# Qwiic_Mux.net
KiCad netlist of a schematic drawn in EAGLE
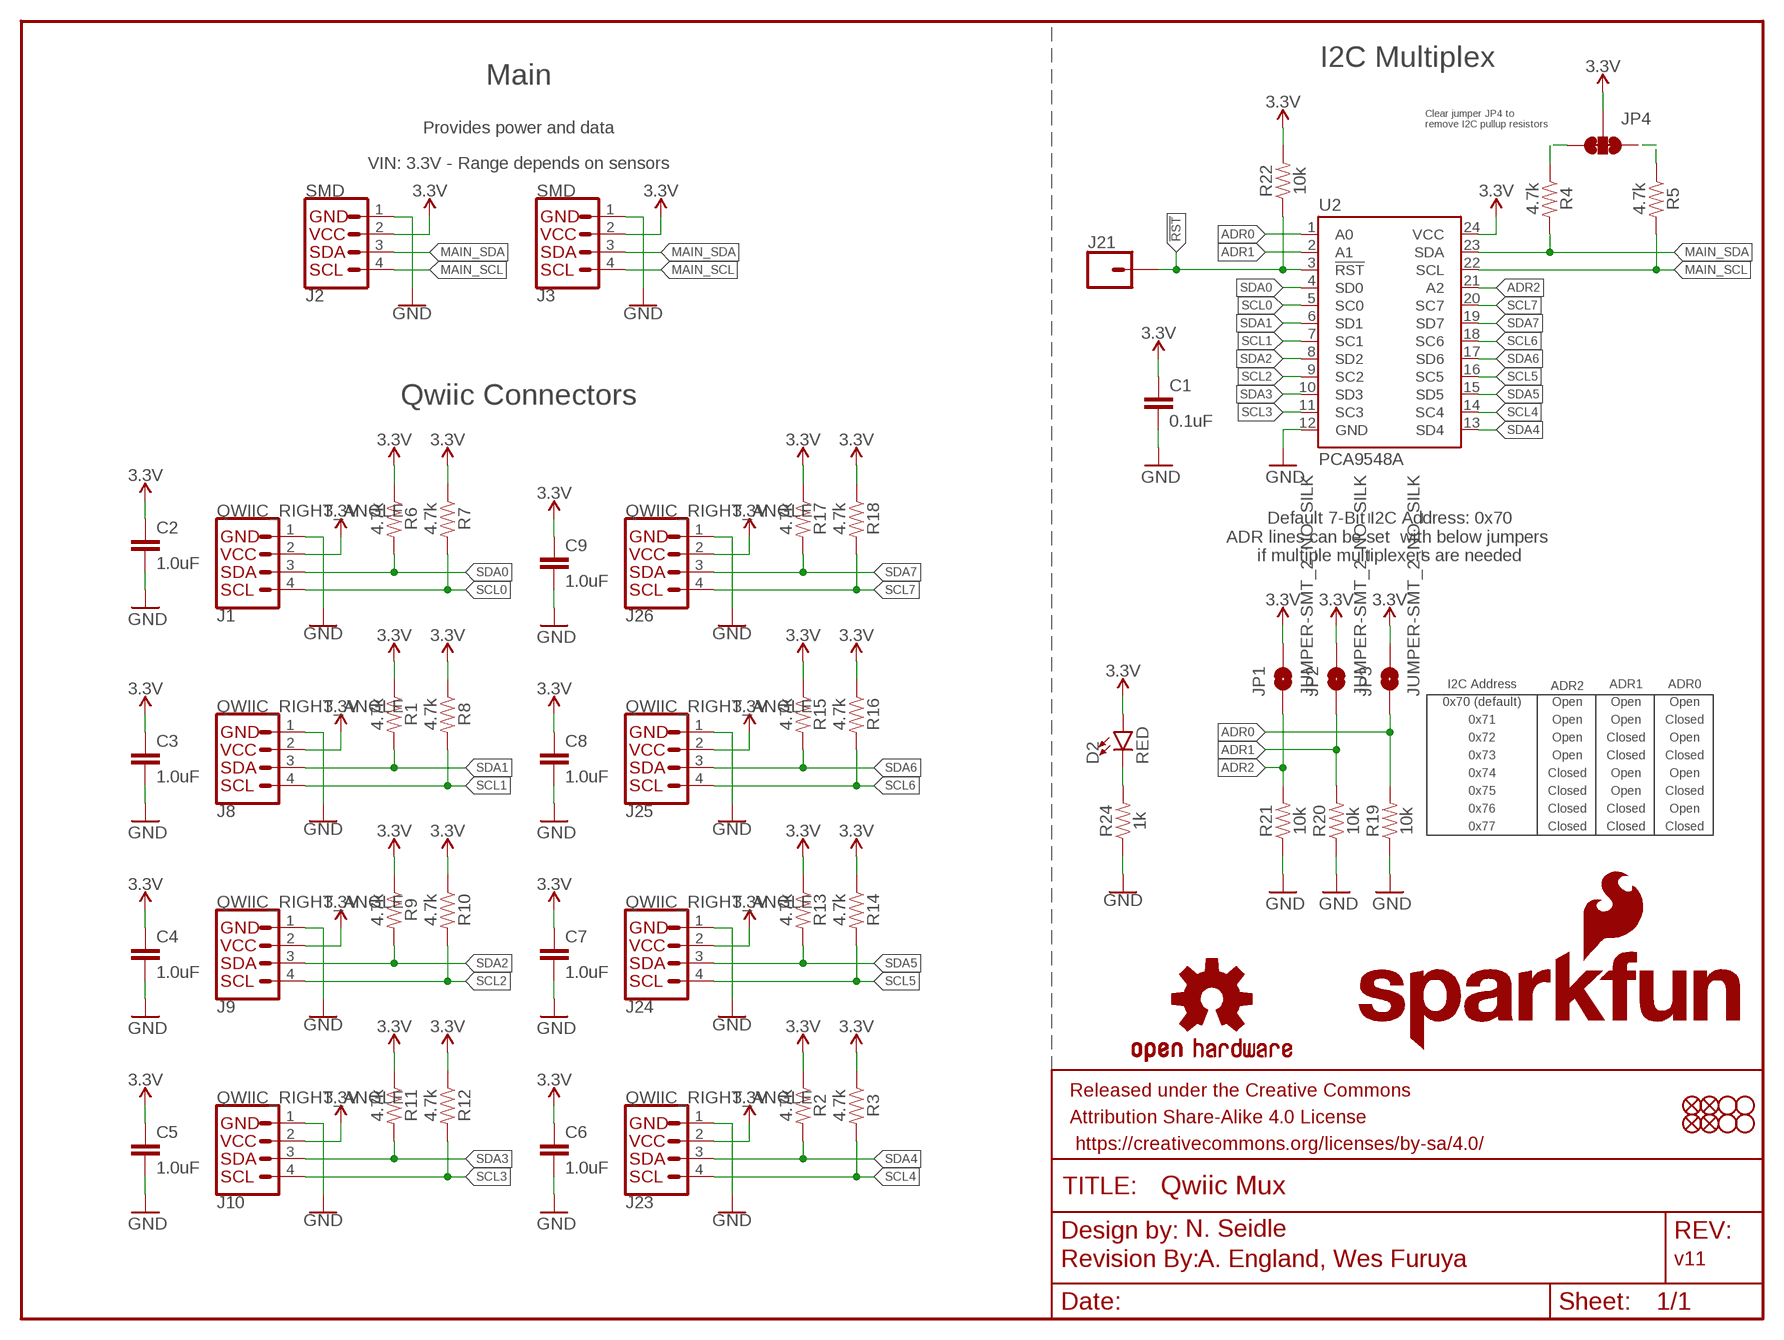
[diagram p0: schematic, sheet 1]

(export (version "E")
  (design (tool "Eeschema 10.0.6"))
  (components
    (comp (ref "C1")
      (value "0.1uF")
      (footprint "eagle-import:0603")
      (libsource (lib "eagle-import") (part "0.1UF-0603-25V-(+80/-20%)"))
    )
    (comp (ref "C2")
      (value "1.0uF")
      (footprint "eagle-import:0603")
      (libsource (lib "eagle-import") (part "1.0UF-0603-16V-10%"))
    )
    (comp (ref "C3")
      (value "1.0uF")
      (footprint "eagle-import:0603")
      (libsource (lib "eagle-import") (part "1.0UF-0603-16V-10%"))
    )
    (comp (ref "C4")
      (value "1.0uF")
      (footprint "eagle-import:0603")
      (libsource (lib "eagle-import") (part "1.0UF-0603-16V-10%"))
    )
    (comp (ref "C5")
      (value "1.0uF")
      (footprint "eagle-import:0603")
      (libsource (lib "eagle-import") (part "1.0UF-0603-16V-10%"))
    )
    (comp (ref "C6")
      (value "1.0uF")
      (footprint "eagle-import:0603")
      (libsource (lib "eagle-import") (part "1.0UF-0603-16V-10%"))
    )
    (comp (ref "C7")
      (value "1.0uF")
      (footprint "eagle-import:0603")
      (libsource (lib "eagle-import") (part "1.0UF-0603-16V-10%"))
    )
    (comp (ref "C8")
      (value "1.0uF")
      (footprint "eagle-import:0603")
      (libsource (lib "eagle-import") (part "1.0UF-0603-16V-10%"))
    )
    (comp (ref "C9")
      (value "1.0uF")
      (footprint "eagle-import:0603")
      (libsource (lib "eagle-import") (part "1.0UF-0603-16V-10%"))
    )
    (comp (ref "D2")
      (value "RED")
      (footprint "eagle-import:LED-0603")
      (libsource (lib "eagle-import") (part "LED-RED0603"))
    )
    (comp (ref "FD1")
      (value "FIDUCIAL1X2")
      (footprint "eagle-import:FIDUCIAL-1X2")
      (libsource (lib "eagle-import") (part "FIDUCIAL1X2"))
    )
    (comp (ref "FD2")
      (value "FIDUCIAL1X2")
      (footprint "eagle-import:FIDUCIAL-1X2")
      (libsource (lib "eagle-import") (part "FIDUCIAL1X2"))
    )
    (comp (ref "FD3")
      (value "FIDUCIAL1X2")
      (footprint "eagle-import:FIDUCIAL-1X2")
      (libsource (lib "eagle-import") (part "FIDUCIAL1X2"))
    )
    (comp (ref "FD4")
      (value "FIDUCIAL1X2")
      (footprint "eagle-import:FIDUCIAL-1X2")
      (libsource (lib "eagle-import") (part "FIDUCIAL1X2"))
    )
    (comp (ref "FRAME1")
      (value "FRAME-LETTER")
      (footprint "eagle-import:CREATIVE_COMMONS")
      (libsource (lib "eagle-import") (part "FRAME-LETTER"))
    )
    (comp (ref "H1")
      (value "STAND-OFF")
      (footprint "eagle-import:STAND-OFF")
      (libsource (lib "eagle-import") (part "STAND-OFF"))
    )
    (comp (ref "H2")
      (value "STAND-OFF")
      (footprint "eagle-import:STAND-OFF")
      (libsource (lib "eagle-import") (part "STAND-OFF"))
    )
    (comp (ref "H3")
      (value "STAND-OFF")
      (footprint "eagle-import:STAND-OFF")
      (libsource (lib "eagle-import") (part "STAND-OFF"))
    )
    (comp (ref "H4")
      (value "STAND-OFF")
      (footprint "eagle-import:STAND-OFF")
      (libsource (lib "eagle-import") (part "STAND-OFF"))
    )
    (comp (ref "J1")
      (value "QWIIC_RIGHT_ANGLE")
      (footprint "eagle-import:JST04_1MM_RA")
      (libsource (lib "eagle-import") (part "QWIIC_CONNECTORJS-1MM"))
    )
    (comp (ref "J2")
      (value "SMD")
      (footprint "eagle-import:1X04_1MM_RA")
      (libsource (lib "eagle-import") (part "I2C_STANDARDJS-1MM"))
    )
    (comp (ref "J3")
      (value "SMD")
      (footprint "eagle-import:1X04_1MM_RA")
      (libsource (lib "eagle-import") (part "I2C_STANDARDJS-1MM"))
    )
    (comp (ref "J8")
      (value "QWIIC_RIGHT_ANGLE")
      (footprint "eagle-import:JST04_1MM_RA")
      (libsource (lib "eagle-import") (part "QWIIC_CONNECTORJS-1MM"))
    )
    (comp (ref "J9")
      (value "QWIIC_RIGHT_ANGLE")
      (footprint "eagle-import:JST04_1MM_RA")
      (libsource (lib "eagle-import") (part "QWIIC_CONNECTORJS-1MM"))
    )
    (comp (ref "J10")
      (value "QWIIC_RIGHT_ANGLE")
      (footprint "eagle-import:JST04_1MM_RA")
      (libsource (lib "eagle-import") (part "QWIIC_CONNECTORJS-1MM"))
    )
    (comp (ref "J21")
      (value "CONN_01PTH_NO_SILK_YES_STOP")
      (footprint "eagle-import:1X01_NO_SILK")
      (libsource (lib "eagle-import") (part "CONN_01PTH_NO_SILK_YES_STOP"))
    )
    (comp (ref "J23")
      (value "QWIIC_RIGHT_ANGLE")
      (footprint "eagle-import:JST04_1MM_RA")
      (libsource (lib "eagle-import") (part "QWIIC_CONNECTORJS-1MM"))
    )
    (comp (ref "J24")
      (value "QWIIC_RIGHT_ANGLE")
      (footprint "eagle-import:JST04_1MM_RA")
      (libsource (lib "eagle-import") (part "QWIIC_CONNECTORJS-1MM"))
    )
    (comp (ref "J25")
      (value "QWIIC_RIGHT_ANGLE")
      (footprint "eagle-import:JST04_1MM_RA")
      (libsource (lib "eagle-import") (part "QWIIC_CONNECTORJS-1MM"))
    )
    (comp (ref "J26")
      (value "QWIIC_RIGHT_ANGLE")
      (footprint "eagle-import:JST04_1MM_RA")
      (libsource (lib "eagle-import") (part "QWIIC_CONNECTORJS-1MM"))
    )
    (comp (ref "JP1")
      (value "JUMPER-SMT_2_NO_SILK")
      (footprint "eagle-import:SMT-JUMPER_2_NO_SILK")
      (libsource (lib "eagle-import") (part "JUMPER-SMT_2_NO_SILK"))
    )
    (comp (ref "JP2")
      (value "JUMPER-SMT_2_NO_SILK")
      (footprint "eagle-import:SMT-JUMPER_2_NO_SILK")
      (libsource (lib "eagle-import") (part "JUMPER-SMT_2_NO_SILK"))
    )
    (comp (ref "JP3")
      (value "JUMPER-SMT_2_NO_SILK")
      (footprint "eagle-import:SMT-JUMPER_2_NO_SILK")
      (libsource (lib "eagle-import") (part "JUMPER-SMT_2_NO_SILK"))
    )
    (comp (ref "JP4")
      (value "JUMPER-SMT_3_2-NC_TRACE_SILK")
      (footprint "eagle-import:SMT-JUMPER_3_2-NC_TRACE_SILK")
      (libsource (lib "eagle-import") (part "JUMPER-SMT_3_2-NC_TRACE_SILK"))
    )
    (comp (ref "LOGO1")
      (value "OSHW-LOGOMINI")
      (footprint "eagle-import:OSHW-LOGO-MINI")
      (libsource (lib "eagle-import") (part "OSHW-LOGOMINI"))
    )
    (comp (ref "LOGO2")
      (value "REVISION")
      (footprint "eagle-import:REVISION")
      (libsource (lib "eagle-import") (part "REVISION"))
    )
    (comp (ref "R1")
      (value "4.7k")
      (footprint "eagle-import:0603")
      (libsource (lib "eagle-import") (part "4.7KOHM-0603-1/10W-1%"))
    )
    (comp (ref "R2")
      (value "4.7k")
      (footprint "eagle-import:0603")
      (libsource (lib "eagle-import") (part "4.7KOHM-0603-1/10W-1%"))
    )
    (comp (ref "R3")
      (value "4.7k")
      (footprint "eagle-import:0603")
      (libsource (lib "eagle-import") (part "4.7KOHM-0603-1/10W-1%"))
    )
    (comp (ref "R4")
      (value "4.7k")
      (footprint "eagle-import:0603")
      (libsource (lib "eagle-import") (part "4.7KOHM-0603-1/10W-1%"))
    )
    (comp (ref "R5")
      (value "4.7k")
      (footprint "eagle-import:0603")
      (libsource (lib "eagle-import") (part "4.7KOHM-0603-1/10W-1%"))
    )
    (comp (ref "R6")
      (value "4.7k")
      (footprint "eagle-import:0603")
      (libsource (lib "eagle-import") (part "4.7KOHM-0603-1/10W-1%"))
    )
    (comp (ref "R7")
      (value "4.7k")
      (footprint "eagle-import:0603")
      (libsource (lib "eagle-import") (part "4.7KOHM-0603-1/10W-1%"))
    )
    (comp (ref "R8")
      (value "4.7k")
      (footprint "eagle-import:0603")
      (libsource (lib "eagle-import") (part "4.7KOHM-0603-1/10W-1%"))
    )
    (comp (ref "R9")
      (value "4.7k")
      (footprint "eagle-import:0603")
      (libsource (lib "eagle-import") (part "4.7KOHM-0603-1/10W-1%"))
    )
    (comp (ref "R10")
      (value "4.7k")
      (footprint "eagle-import:0603")
      (libsource (lib "eagle-import") (part "4.7KOHM-0603-1/10W-1%"))
    )
    (comp (ref "R11")
      (value "4.7k")
      (footprint "eagle-import:0603")
      (libsource (lib "eagle-import") (part "4.7KOHM-0603-1/10W-1%"))
    )
    (comp (ref "R12")
      (value "4.7k")
      (footprint "eagle-import:0603")
      (libsource (lib "eagle-import") (part "4.7KOHM-0603-1/10W-1%"))
    )
    (comp (ref "R13")
      (value "4.7k")
      (footprint "eagle-import:0603")
      (libsource (lib "eagle-import") (part "4.7KOHM-0603-1/10W-1%"))
    )
    (comp (ref "R14")
      (value "4.7k")
      (footprint "eagle-import:0603")
      (libsource (lib "eagle-import") (part "4.7KOHM-0603-1/10W-1%"))
    )
    (comp (ref "R15")
      (value "4.7k")
      (footprint "eagle-import:0603")
      (libsource (lib "eagle-import") (part "4.7KOHM-0603-1/10W-1%"))
    )
    (comp (ref "R16")
      (value "4.7k")
      (footprint "eagle-import:0603")
      (libsource (lib "eagle-import") (part "4.7KOHM-0603-1/10W-1%"))
    )
    (comp (ref "R17")
      (value "4.7k")
      (footprint "eagle-import:0603")
      (libsource (lib "eagle-import") (part "4.7KOHM-0603-1/10W-1%"))
    )
    (comp (ref "R18")
      (value "4.7k")
      (footprint "eagle-import:0603")
      (libsource (lib "eagle-import") (part "4.7KOHM-0603-1/10W-1%"))
    )
    (comp (ref "R19")
      (value "10k")
      (footprint "eagle-import:0603")
      (libsource (lib "eagle-import") (part "10KOHM-0603-1/10W-1%"))
    )
    (comp (ref "R20")
      (value "10k")
      (footprint "eagle-import:0603")
      (libsource (lib "eagle-import") (part "10KOHM-0603-1/10W-1%"))
    )
    (comp (ref "R21")
      (value "10k")
      (footprint "eagle-import:0603")
      (libsource (lib "eagle-import") (part "10KOHM-0603-1/10W-1%"))
    )
    (comp (ref "R22")
      (value "10k")
      (footprint "eagle-import:0603")
      (libsource (lib "eagle-import") (part "10KOHM-0603-1/10W-1%"))
    )
    (comp (ref "R24")
      (value "1k")
      (footprint "eagle-import:0603")
      (libsource (lib "eagle-import") (part "1KOHM-0603-1/10W-1%"))
    )
    (comp (ref "U$1")
      (value "SFE_LOGO_NAME_FLAME.1_INCH")
      (footprint "eagle-import:SFE_LOGO_NAME_FLAME_.1")
      (libsource (lib "eagle-import") (part "SFE_LOGO_NAME_FLAME.1_INCH"))
    )
    (comp (ref "U$2")
      (value "SFE_LOGO_NAME_FLAME.1_INCH")
      (footprint "eagle-import:SFE_LOGO_NAME_FLAME_.1")
      (libsource (lib "eagle-import") (part "SFE_LOGO_NAME_FLAME.1_INCH"))
    )
    (comp (ref "U2")
      (value "PCA9548A")
      (footprint "eagle-import:TSSOP28")
      (libsource (lib "eagle-import") (part "PCA9548A"))
    )
  )
  (nets
    (net (code "1") (name "/~{RST}") (class "Default")
      (node (ref "J21") (pin "1") (pinfunction "1_1") (pintype "passive"))
      (node (ref "R22") (pin "1") (pinfunction "1_1") (pintype "passive"))
      (node (ref "U2") (pin "3") (pinfunction "~{RST}_3") (pintype "bidirectional"))
    )
    (net (code "2") (name "3.3V") (class "Default")
      (node (ref "C1") (pin "1") (pinfunction "1_1") (pintype "passive"))
      (node (ref "C2") (pin "1") (pinfunction "1_1") (pintype "passive"))
      (node (ref "C3") (pin "1") (pinfunction "1_1") (pintype "passive"))
      (node (ref "C4") (pin "1") (pinfunction "1_1") (pintype "passive"))
      (node (ref "C5") (pin "1") (pinfunction "1_1") (pintype "passive"))
      (node (ref "C6") (pin "1") (pinfunction "1_1") (pintype "passive"))
      (node (ref "C7") (pin "1") (pinfunction "1_1") (pintype "passive"))
      (node (ref "C8") (pin "1") (pinfunction "1_1") (pintype "passive"))
      (node (ref "C9") (pin "1") (pinfunction "1_1") (pintype "passive"))
      (node (ref "D2") (pin "A") (pinfunction "A_A") (pintype "passive"))
      (node (ref "J1") (pin "2") (pinfunction "2_2") (pintype "power_in"))
      (node (ref "J10") (pin "2") (pinfunction "2_2") (pintype "power_in"))
      (node (ref "J2") (pin "2") (pinfunction "VCC_2") (pintype "power_in"))
      (node (ref "J23") (pin "2") (pinfunction "2_2") (pintype "power_in"))
      (node (ref "J24") (pin "2") (pinfunction "2_2") (pintype "power_in"))
      (node (ref "J25") (pin "2") (pinfunction "2_2") (pintype "power_in"))
      (node (ref "J26") (pin "2") (pinfunction "2_2") (pintype "power_in"))
      (node (ref "J3") (pin "2") (pinfunction "VCC_2") (pintype "power_in"))
      (node (ref "J8") (pin "2") (pinfunction "2_2") (pintype "power_in"))
      (node (ref "J9") (pin "2") (pinfunction "2_2") (pintype "power_in"))
      (node (ref "JP1") (pin "2") (pinfunction "2_2") (pintype "passive"))
      (node (ref "JP2") (pin "2") (pinfunction "2_2") (pintype "passive"))
      (node (ref "JP3") (pin "2") (pinfunction "2_2") (pintype "passive"))
      (node (ref "JP4") (pin "2") (pinfunction "2_2") (pintype "passive"))
      (node (ref "R1") (pin "1") (pinfunction "1_1") (pintype "passive"))
      (node (ref "R10") (pin "1") (pinfunction "1_1") (pintype "passive"))
      (node (ref "R11") (pin "1") (pinfunction "1_1") (pintype "passive"))
      (node (ref "R12") (pin "1") (pinfunction "1_1") (pintype "passive"))
      (node (ref "R13") (pin "1") (pinfunction "1_1") (pintype "passive"))
      (node (ref "R14") (pin "1") (pinfunction "1_1") (pintype "passive"))
      (node (ref "R15") (pin "1") (pinfunction "1_1") (pintype "passive"))
      (node (ref "R16") (pin "1") (pinfunction "1_1") (pintype "passive"))
      (node (ref "R17") (pin "1") (pinfunction "1_1") (pintype "passive"))
      (node (ref "R18") (pin "1") (pinfunction "1_1") (pintype "passive"))
      (node (ref "R2") (pin "1") (pinfunction "1_1") (pintype "passive"))
      (node (ref "R22") (pin "2") (pinfunction "2_2") (pintype "passive"))
      (node (ref "R3") (pin "1") (pinfunction "1_1") (pintype "passive"))
      (node (ref "R6") (pin "1") (pinfunction "1_1") (pintype "passive"))
      (node (ref "R7") (pin "1") (pinfunction "1_1") (pintype "passive"))
      (node (ref "R8") (pin "1") (pinfunction "1_1") (pintype "passive"))
      (node (ref "R9") (pin "1") (pinfunction "1_1") (pintype "passive"))
      (node (ref "U2") (pin "24") (pinfunction "VCC_24") (pintype "bidirectional"))
    )
    (net (code "3") (name "ADR0") (class "Default")
      (node (ref "JP3") (pin "1") (pinfunction "1_1") (pintype "passive"))
      (node (ref "R19") (pin "2") (pinfunction "2_2") (pintype "passive"))
      (node (ref "U2") (pin "1") (pinfunction "A0_1") (pintype "bidirectional"))
    )
    (net (code "4") (name "ADR1") (class "Default")
      (node (ref "JP2") (pin "1") (pinfunction "1_1") (pintype "passive"))
      (node (ref "R20") (pin "2") (pinfunction "2_2") (pintype "passive"))
      (node (ref "U2") (pin "2") (pinfunction "A1_2") (pintype "bidirectional"))
    )
    (net (code "5") (name "ADR2") (class "Default")
      (node (ref "JP1") (pin "1") (pinfunction "1_1") (pintype "passive"))
      (node (ref "R21") (pin "2") (pinfunction "2_2") (pintype "passive"))
      (node (ref "U2") (pin "21") (pinfunction "A2_21") (pintype "bidirectional"))
    )
    (net (code "6") (name "GND") (class "Default")
      (node (ref "C1") (pin "2") (pinfunction "2_2") (pintype "passive"))
      (node (ref "C2") (pin "2") (pinfunction "2_2") (pintype "passive"))
      (node (ref "C3") (pin "2") (pinfunction "2_2") (pintype "passive"))
      (node (ref "C4") (pin "2") (pinfunction "2_2") (pintype "passive"))
      (node (ref "C5") (pin "2") (pinfunction "2_2") (pintype "passive"))
      (node (ref "C6") (pin "2") (pinfunction "2_2") (pintype "passive"))
      (node (ref "C7") (pin "2") (pinfunction "2_2") (pintype "passive"))
      (node (ref "C8") (pin "2") (pinfunction "2_2") (pintype "passive"))
      (node (ref "C9") (pin "2") (pinfunction "2_2") (pintype "passive"))
      (node (ref "J1") (pin "1") (pinfunction "1_1") (pintype "power_in"))
      (node (ref "J10") (pin "1") (pinfunction "1_1") (pintype "power_in"))
      (node (ref "J2") (pin "1") (pinfunction "GND_1") (pintype "power_in"))
      (node (ref "J23") (pin "1") (pinfunction "1_1") (pintype "power_in"))
      (node (ref "J24") (pin "1") (pinfunction "1_1") (pintype "power_in"))
      (node (ref "J25") (pin "1") (pinfunction "1_1") (pintype "power_in"))
      (node (ref "J26") (pin "1") (pinfunction "1_1") (pintype "power_in"))
      (node (ref "J3") (pin "1") (pinfunction "GND_1") (pintype "power_in"))
      (node (ref "J8") (pin "1") (pinfunction "1_1") (pintype "power_in"))
      (node (ref "J9") (pin "1") (pinfunction "1_1") (pintype "power_in"))
      (node (ref "R19") (pin "1") (pinfunction "1_1") (pintype "passive"))
      (node (ref "R20") (pin "1") (pinfunction "1_1") (pintype "passive"))
      (node (ref "R21") (pin "1") (pinfunction "1_1") (pintype "passive"))
      (node (ref "R24") (pin "1") (pinfunction "1_1") (pintype "passive"))
      (node (ref "U2") (pin "12") (pinfunction "GND_12") (pintype "bidirectional"))
    )
    (net (code "7") (name "MAIN_SCL") (class "Default")
      (node (ref "J2") (pin "4") (pinfunction "SCL_4") (pintype "passive"))
      (node (ref "J3") (pin "4") (pinfunction "SCL_4") (pintype "passive"))
      (node (ref "R5") (pin "2") (pinfunction "2_2") (pintype "passive"))
      (node (ref "U2") (pin "22") (pinfunction "SCL_22") (pintype "bidirectional"))
    )
    (net (code "8") (name "MAIN_SDA") (class "Default")
      (node (ref "J2") (pin "3") (pinfunction "SDA_3") (pintype "passive"))
      (node (ref "J3") (pin "3") (pinfunction "SDA_3") (pintype "passive"))
      (node (ref "R4") (pin "2") (pinfunction "2_2") (pintype "passive"))
      (node (ref "U2") (pin "23") (pinfunction "SDA_23") (pintype "bidirectional"))
    )
    (net (code "9") (name "Net-(D2-PadC)") (class "Default")
      (node (ref "D2") (pin "C") (pinfunction "C_C") (pintype "passive"))
      (node (ref "R24") (pin "2") (pinfunction "2_2") (pintype "passive"))
    )
    (net (code "10") (name "Net-(JP4-Pad1)") (class "Default")
      (node (ref "JP4") (pin "1") (pinfunction "1_1") (pintype "passive"))
      (node (ref "R5") (pin "1") (pinfunction "1_1") (pintype "passive"))
    )
    (net (code "11") (name "Net-(JP4-Pad3)") (class "Default")
      (node (ref "JP4") (pin "3") (pinfunction "3_3") (pintype "passive"))
      (node (ref "R4") (pin "1") (pinfunction "1_1") (pintype "passive"))
    )
    (net (code "12") (name "SCL0") (class "Default")
      (node (ref "J1") (pin "4") (pinfunction "4_4") (pintype "passive"))
      (node (ref "R7") (pin "2") (pinfunction "2_2") (pintype "passive"))
      (node (ref "U2") (pin "5") (pinfunction "SC0_5") (pintype "bidirectional"))
    )
    (net (code "13") (name "SCL1") (class "Default")
      (node (ref "J8") (pin "4") (pinfunction "4_4") (pintype "passive"))
      (node (ref "R8") (pin "2") (pinfunction "2_2") (pintype "passive"))
      (node (ref "U2") (pin "7") (pinfunction "SC1_7") (pintype "bidirectional"))
    )
    (net (code "14") (name "SCL2") (class "Default")
      (node (ref "J9") (pin "4") (pinfunction "4_4") (pintype "passive"))
      (node (ref "R10") (pin "2") (pinfunction "2_2") (pintype "passive"))
      (node (ref "U2") (pin "9") (pinfunction "SC2_9") (pintype "bidirectional"))
    )
    (net (code "15") (name "SCL3") (class "Default")
      (node (ref "J10") (pin "4") (pinfunction "4_4") (pintype "passive"))
      (node (ref "R12") (pin "2") (pinfunction "2_2") (pintype "passive"))
      (node (ref "U2") (pin "11") (pinfunction "SC3_11") (pintype "bidirectional"))
    )
    (net (code "16") (name "SCL4") (class "Default")
      (node (ref "J23") (pin "4") (pinfunction "4_4") (pintype "passive"))
      (node (ref "R3") (pin "2") (pinfunction "2_2") (pintype "passive"))
      (node (ref "U2") (pin "14") (pinfunction "SC4_14") (pintype "bidirectional"))
    )
    (net (code "17") (name "SCL5") (class "Default")
      (node (ref "J24") (pin "4") (pinfunction "4_4") (pintype "passive"))
      (node (ref "R14") (pin "2") (pinfunction "2_2") (pintype "passive"))
      (node (ref "U2") (pin "16") (pinfunction "SC5_16") (pintype "bidirectional"))
    )
    (net (code "18") (name "SCL6") (class "Default")
      (node (ref "J25") (pin "4") (pinfunction "4_4") (pintype "passive"))
      (node (ref "R16") (pin "2") (pinfunction "2_2") (pintype "passive"))
      (node (ref "U2") (pin "18") (pinfunction "SC6_18") (pintype "bidirectional"))
    )
    (net (code "19") (name "SCL7") (class "Default")
      (node (ref "J26") (pin "4") (pinfunction "4_4") (pintype "passive"))
      (node (ref "R18") (pin "2") (pinfunction "2_2") (pintype "passive"))
      (node (ref "U2") (pin "20") (pinfunction "SC7_20") (pintype "bidirectional"))
    )
    (net (code "20") (name "SDA0") (class "Default")
      (node (ref "J1") (pin "3") (pinfunction "3_3") (pintype "passive"))
      (node (ref "R6") (pin "2") (pinfunction "2_2") (pintype "passive"))
      (node (ref "U2") (pin "4") (pinfunction "SD0_4") (pintype "bidirectional"))
    )
    (net (code "21") (name "SDA1") (class "Default")
      (node (ref "J8") (pin "3") (pinfunction "3_3") (pintype "passive"))
      (node (ref "R1") (pin "2") (pinfunction "2_2") (pintype "passive"))
      (node (ref "U2") (pin "6") (pinfunction "SD1_6") (pintype "bidirectional"))
    )
    (net (code "22") (name "SDA2") (class "Default")
      (node (ref "J9") (pin "3") (pinfunction "3_3") (pintype "passive"))
      (node (ref "R9") (pin "2") (pinfunction "2_2") (pintype "passive"))
      (node (ref "U2") (pin "8") (pinfunction "SD2_8") (pintype "bidirectional"))
    )
    (net (code "23") (name "SDA3") (class "Default")
      (node (ref "J10") (pin "3") (pinfunction "3_3") (pintype "passive"))
      (node (ref "R11") (pin "2") (pinfunction "2_2") (pintype "passive"))
      (node (ref "U2") (pin "10") (pinfunction "SD3_10") (pintype "bidirectional"))
    )
    (net (code "24") (name "SDA4") (class "Default")
      (node (ref "J23") (pin "3") (pinfunction "3_3") (pintype "passive"))
      (node (ref "R2") (pin "2") (pinfunction "2_2") (pintype "passive"))
      (node (ref "U2") (pin "13") (pinfunction "SD4_13") (pintype "bidirectional"))
    )
    (net (code "25") (name "SDA5") (class "Default")
      (node (ref "J24") (pin "3") (pinfunction "3_3") (pintype "passive"))
      (node (ref "R13") (pin "2") (pinfunction "2_2") (pintype "passive"))
      (node (ref "U2") (pin "15") (pinfunction "SD5_15") (pintype "bidirectional"))
    )
    (net (code "26") (name "SDA6") (class "Default")
      (node (ref "J25") (pin "3") (pinfunction "3_3") (pintype "passive"))
      (node (ref "R15") (pin "2") (pinfunction "2_2") (pintype "passive"))
      (node (ref "U2") (pin "17") (pinfunction "SD6_17") (pintype "bidirectional"))
    )
    (net (code "27") (name "SDA7") (class "Default")
      (node (ref "J26") (pin "3") (pinfunction "3_3") (pintype "passive"))
      (node (ref "R17") (pin "2") (pinfunction "2_2") (pintype "passive"))
      (node (ref "U2") (pin "19") (pinfunction "SD7_19") (pintype "bidirectional"))
    )
  )
)
